# NitroxAnalyzer.net
KiCad netlist of a schematic drawn in EAGLE
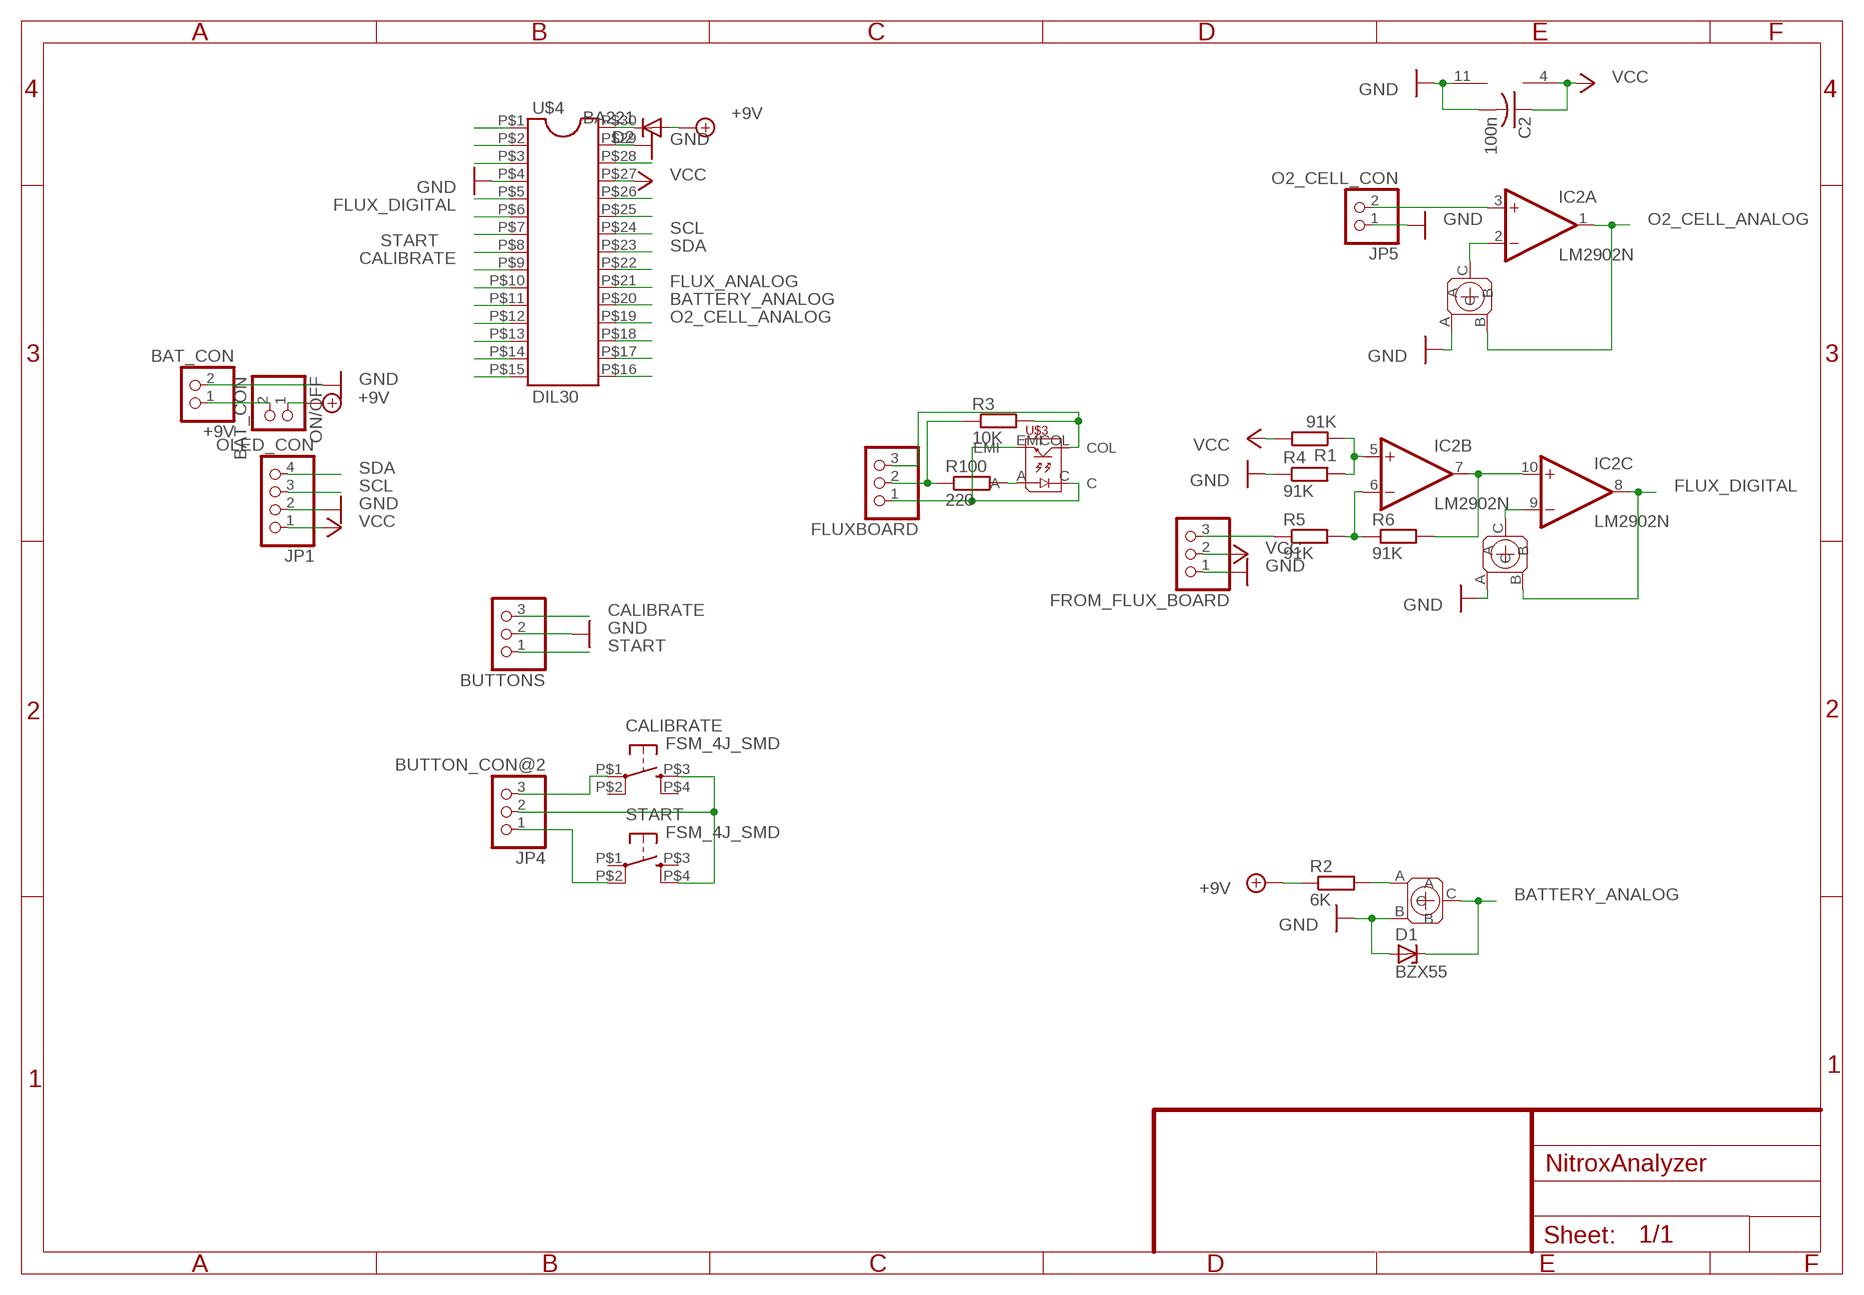
[diagram p0: schematic, sheet 1]

(export (version "E")
  (design (tool "Eeschema 10.0.6"))
  (components
    (comp (ref "+9V")
      (value "BAT_CON")
      (footprint "eagle-import:1X02")
      (libsource (lib "eagle-import") (part "PINHD-1X2"))
    )
    (comp (ref "BUTTONS")
      (value "PINHD-1X3")
      (footprint "eagle-import:1X03")
      (libsource (lib "eagle-import") (part "PINHD-1X3"))
    )
    (comp (ref "C2")
      (value "100n")
      (footprint "eagle-import:C1206")
      (libsource (lib "eagle-import") (part "C-USC1206"))
    )
    (comp (ref "CALIBRATE")
      (value "FSM_4J_SMD")
      (footprint "eagle-import:B3F-10XX")
      (libsource (lib "eagle-import") (part "FSM_4J_SMD"))
    )
    (comp (ref "D1")
      (value "BZX55")
      (footprint "eagle-import:DO35Z10")
      (libsource (lib "eagle-import") (part "BZX55"))
    )
    (comp (ref "D2")
      (value "BA221")
      (footprint "eagle-import:DO35-10")
      (libsource (lib "eagle-import") (part "BA221"))
    )
    (comp (ref "FLUXBOARD")
      (value "PINHD-1X3")
      (footprint "eagle-import:1X03")
      (libsource (lib "eagle-import") (part "PINHD-1X3"))
    )
    (comp (ref "FROM_FLUX_BOARD")
      (value "PINHD-1X3")
      (footprint "eagle-import:1X03")
      (libsource (lib "eagle-import") (part "PINHD-1X3"))
    )
    (comp (ref "IC2")
      (value "LM2902N")
      (footprint "eagle-import:DIL14")
      (libsource (lib "eagle-import") (part "LM2902N"))
    )
    (comp (ref "JP1")
      (value "OLED_CON")
      (footprint "eagle-import:1X04")
      (libsource (lib "eagle-import") (part "PINHD-1X4"))
    )
    (comp (ref "JP4")
      (value "BUTTON_CON@2")
      (footprint "eagle-import:1X03")
      (libsource (lib "eagle-import") (part "PINHD-1X3"))
    )
    (comp (ref "JP5")
      (value "O2_CELL_CON")
      (footprint "eagle-import:1X02")
      (libsource (lib "eagle-import") (part "PINHD-1X2"))
    )
    (comp (ref "ON/OFF")
      (value "BAT_CON")
      (footprint "eagle-import:1X02")
      (libsource (lib "eagle-import") (part "PINHD-1X2"))
    )
    (comp (ref "R1")
      (value "91K")
      (footprint "eagle-import:R0805")
      (libsource (lib "eagle-import") (part "R-EU_R0805"))
    )
    (comp (ref "R2")
      (value "6K")
      (footprint "eagle-import:R1206")
      (libsource (lib "eagle-import") (part "R-EU_R1206"))
    )
    (comp (ref "R3")
      (value "10K")
      (footprint "eagle-import:R1206")
      (libsource (lib "eagle-import") (part "R-EU_R1206"))
    )
    (comp (ref "R4")
      (value "91K")
      (footprint "eagle-import:R0805")
      (libsource (lib "eagle-import") (part "R-EU_R0805"))
    )
    (comp (ref "R5")
      (value "91K")
      (footprint "eagle-import:R0805")
      (libsource (lib "eagle-import") (part "R-EU_R0805"))
    )
    (comp (ref "R6")
      (value "91K")
      (footprint "eagle-import:R0805")
      (libsource (lib "eagle-import") (part "R-EU_R0805"))
    )
    (comp (ref "R100")
      (value "220")
      (footprint "eagle-import:R1206")
      (libsource (lib "eagle-import") (part "R-EU_R1206"))
    )
    (comp (ref "START")
      (value "FSM_4J_SMD")
      (footprint "eagle-import:B3F-10XX")
      (libsource (lib "eagle-import") (part "FSM_4J_SMD"))
    )
    (comp (ref "U$1")
      (value "10K")
      (footprint "eagle-import:PT6KV")
      (libsource (lib "eagle-import") (part "PT6KV"))
    )
    (comp (ref "U$2")
      (value "100K")
      (footprint "eagle-import:PT6KV")
      (libsource (lib "eagle-import") (part "PT6KV"))
    )
    (comp (ref "U$3")
      (value "ITR8307")
      (footprint "eagle-import:4PIN")
      (libsource (lib "eagle-import") (part "ITR8307"))
    )
    (comp (ref "U$4")
      (value "DIL30")
      (footprint "eagle-import:DIL30")
      (libsource (lib "eagle-import") (part "DIL30"))
    )
    (comp (ref "U$5")
      (value "100K")
      (footprint "eagle-import:PT6KV")
      (libsource (lib "eagle-import") (part "PT6KV"))
    )
  )
  (nets
    (net (code "1") (name "+9V") (class "Default")
      (node (ref "D2") (pin "A") (pinfunction "A_A") (pintype "passive"))
      (node (ref "ON/OFF") (pin "1") (pinfunction "1_1") (pintype "passive"))
      (node (ref "R2") (pin "1") (pinfunction "1_1") (pintype "passive"))
    )
    (net (code "2") (name "/BATTERY_ANALOG") (class "Default")
      (node (ref "D1") (pin "C") (pinfunction "C_C") (pintype "passive"))
      (node (ref "U$1") (pin "C") (pinfunction "C_C") (pintype "bidirectional"))
      (node (ref "U$4") (pin "P$20") (pinfunction "20_P$20") (pintype "passive"))
    )
    (net (code "3") (name "/CALIBRATE") (class "Default")
      (node (ref "BUTTONS") (pin "3") (pinfunction "3_3") (pintype "passive"))
      (node (ref "U$4") (pin "P$8") (pinfunction "8_P$8") (pintype "passive"))
    )
    (net (code "4") (name "/FLUX_ANALOG") (class "Default")
      (node (ref "U$4") (pin "P$21") (pinfunction "21_P$21") (pintype "passive"))
    )
    (net (code "5") (name "/FLUX_DIGITAL") (class "Default")
      (node (ref "IC2") (pin "8") (pinfunction "OUT_8") (pintype "output"))
      (node (ref "U$4") (pin "P$5") (pinfunction "5_P$5") (pintype "passive"))
      (node (ref "U$5") (pin "B") (pinfunction "B_B") (pintype "bidirectional"))
    )
    (net (code "6") (name "/O2_CELL_ANALOG") (class "Default")
      (node (ref "IC2") (pin "1") (pinfunction "OUT_1") (pintype "output"))
      (node (ref "U$2") (pin "B") (pinfunction "B_B") (pintype "bidirectional"))
      (node (ref "U$4") (pin "P$19") (pinfunction "19_P$19") (pintype "passive"))
    )
    (net (code "7") (name "/SCL") (class "Default")
      (node (ref "JP1") (pin "3") (pinfunction "3_3") (pintype "passive"))
      (node (ref "U$4") (pin "P$24") (pinfunction "24_P$24") (pintype "passive"))
    )
    (net (code "8") (name "/SDA") (class "Default")
      (node (ref "JP1") (pin "4") (pinfunction "4_4") (pintype "passive"))
      (node (ref "U$4") (pin "P$23") (pinfunction "23_P$23") (pintype "passive"))
    )
    (net (code "9") (name "/START") (class "Default")
      (node (ref "BUTTONS") (pin "1") (pinfunction "1_1") (pintype "passive"))
      (node (ref "U$4") (pin "P$7") (pinfunction "7_P$7") (pintype "passive"))
    )
    (net (code "10") (name "GND") (class "Default")
      (node (ref "+9V") (pin "2") (pinfunction "2_2") (pintype "passive"))
      (node (ref "BUTTONS") (pin "2") (pinfunction "2_2") (pintype "passive"))
      (node (ref "C2") (pin "2") (pinfunction "2_2") (pintype "passive"))
      (node (ref "D1") (pin "A") (pinfunction "A_A") (pintype "passive"))
      (node (ref "FROM_FLUX_BOARD") (pin "1") (pinfunction "1_1") (pintype "passive"))
      (node (ref "IC2") (pin "11") (pinfunction "V-_11") (pintype "power_in"))
      (node (ref "JP1") (pin "2") (pinfunction "2_2") (pintype "passive"))
      (node (ref "JP5") (pin "1") (pinfunction "1_1") (pintype "passive"))
      (node (ref "R4") (pin "1") (pinfunction "1_1") (pintype "passive"))
      (node (ref "U$1") (pin "B") (pinfunction "B_B") (pintype "bidirectional"))
      (node (ref "U$2") (pin "A") (pinfunction "A_A") (pintype "bidirectional"))
      (node (ref "U$4") (pin "P$29") (pinfunction "29_P$29") (pintype "passive"))
      (node (ref "U$4") (pin "P$4") (pinfunction "4_P$4") (pintype "passive"))
      (node (ref "U$5") (pin "A") (pinfunction "A_A") (pintype "bidirectional"))
    )
    (net (code "11") (name "Net-(+9V-Pad1)") (class "Default")
      (node (ref "+9V") (pin "1") (pinfunction "1_1") (pintype "passive"))
      (node (ref "ON/OFF") (pin "2") (pinfunction "2_2") (pintype "passive"))
    )
    (net (code "12") (name "Net-(CALIBRATE-P)") (class "Default")
      (node (ref "CALIBRATE") (pin "P$1") (pinfunction "P_P$1") (pintype "passive"))
      (node (ref "JP4") (pin "3") (pinfunction "3_3") (pintype "passive"))
    )
    (net (code "13") (name "Net-(CALIBRATE-S)") (class "Default")
      (node (ref "CALIBRATE") (pin "P$3") (pinfunction "S_P$3") (pintype "passive"))
      (node (ref "JP4") (pin "2") (pinfunction "2_2") (pintype "passive"))
      (node (ref "START") (pin "P$4") (pinfunction "S1_P$4") (pintype "passive"))
    )
    (net (code "14") (name "Net-(FLUXBOARD-Pad1)") (class "Default")
      (node (ref "FLUXBOARD") (pin "1") (pinfunction "1_1") (pintype "passive"))
      (node (ref "U$3") (pin "C") (pinfunction "C_C") (pintype "power_in"))
      (node (ref "U$3") (pin "EMI") (pinfunction "EMI_EMI") (pintype "power_in"))
    )
    (net (code "15") (name "Net-(FLUXBOARD-Pad2)") (class "Default")
      (node (ref "FLUXBOARD") (pin "2") (pinfunction "2_2") (pintype "passive"))
      (node (ref "R100") (pin "1") (pinfunction "1_1") (pintype "passive"))
      (node (ref "R3") (pin "1") (pinfunction "1_1") (pintype "passive"))
    )
    (net (code "16") (name "Net-(FLUXBOARD-Pad3)") (class "Default")
      (node (ref "FLUXBOARD") (pin "3") (pinfunction "3_3") (pintype "passive"))
      (node (ref "R3") (pin "2") (pinfunction "2_2") (pintype "passive"))
      (node (ref "U$3") (pin "COL") (pinfunction "COL_COL") (pintype "power_in"))
    )
    (net (code "17") (name "Net-(FROM_FLUX_BOARD-Pad3)") (class "Default")
      (node (ref "FROM_FLUX_BOARD") (pin "3") (pinfunction "3_3") (pintype "passive"))
      (node (ref "R5") (pin "1") (pinfunction "1_1") (pintype "passive"))
    )
    (net (code "18") (name "Net-(IC2A-+IN)") (class "Default")
      (node (ref "IC2") (pin "3") (pinfunction "+IN_3") (pintype "input"))
      (node (ref "JP5") (pin "2") (pinfunction "2_2") (pintype "passive"))
    )
    (net (code "19") (name "Net-(IC2A--IN)") (class "Default")
      (node (ref "IC2") (pin "2") (pinfunction "-IN_2") (pintype "input"))
      (node (ref "U$2") (pin "C") (pinfunction "C_C") (pintype "bidirectional"))
    )
    (net (code "20") (name "Net-(IC2B-+IN)") (class "Default")
      (node (ref "IC2") (pin "5") (pinfunction "+IN_5") (pintype "input"))
      (node (ref "R1") (pin "1") (pinfunction "1_1") (pintype "passive"))
      (node (ref "R4") (pin "2") (pinfunction "2_2") (pintype "passive"))
    )
    (net (code "21") (name "Net-(IC2B--IN)") (class "Default")
      (node (ref "IC2") (pin "6") (pinfunction "-IN_6") (pintype "input"))
      (node (ref "R5") (pin "2") (pinfunction "2_2") (pintype "passive"))
      (node (ref "R6") (pin "1") (pinfunction "1_1") (pintype "passive"))
    )
    (net (code "22") (name "Net-(IC2B-OUT)") (class "Default")
      (node (ref "IC2") (pin "10") (pinfunction "+IN_10") (pintype "input"))
      (node (ref "IC2") (pin "7") (pinfunction "OUT_7") (pintype "output"))
      (node (ref "R6") (pin "2") (pinfunction "2_2") (pintype "passive"))
    )
    (net (code "23") (name "Net-(IC2C--IN)") (class "Default")
      (node (ref "IC2") (pin "9") (pinfunction "-IN_9") (pintype "input"))
      (node (ref "U$5") (pin "C") (pinfunction "C_C") (pintype "bidirectional"))
    )
    (net (code "24") (name "Net-(R2-Pad2)") (class "Default")
      (node (ref "R2") (pin "2") (pinfunction "2_2") (pintype "passive"))
      (node (ref "U$1") (pin "A") (pinfunction "A_A") (pintype "bidirectional"))
    )
    (net (code "25") (name "Net-(R100-Pad2)") (class "Default")
      (node (ref "R100") (pin "2") (pinfunction "2_2") (pintype "passive"))
      (node (ref "U$3") (pin "A") (pinfunction "A_A") (pintype "power_in"))
    )
    (net (code "26") (name "Net-(START-P1)") (class "Default")
      (node (ref "JP4") (pin "1") (pinfunction "1_1") (pintype "passive"))
      (node (ref "START") (pin "P$2") (pinfunction "P1_P$2") (pintype "passive"))
    )
    (net (code "27") (name "Net-(U$4-30)") (class "Default")
      (node (ref "D2") (pin "C") (pinfunction "C_C") (pintype "passive"))
      (node (ref "U$4") (pin "P$30") (pinfunction "30_P$30") (pintype "passive"))
    )
    (net (code "28") (name "VCC") (class "Default")
      (node (ref "C2") (pin "1") (pinfunction "1_1") (pintype "passive"))
      (node (ref "FROM_FLUX_BOARD") (pin "2") (pinfunction "2_2") (pintype "passive"))
      (node (ref "IC2") (pin "4") (pinfunction "V+_4") (pintype "power_in"))
      (node (ref "JP1") (pin "1") (pinfunction "1_1") (pintype "passive"))
      (node (ref "R1") (pin "2") (pinfunction "2_2") (pintype "passive"))
      (node (ref "U$4") (pin "P$27") (pinfunction "27_P$27") (pintype "passive"))
    )
    (net (code "29") (name "unconnected-(CALIBRATE-P1-PadP$2)") (class "Default")
      (node (ref "CALIBRATE") (pin "P$2") (pinfunction "P1_P$2") (pintype "passive"))
    )
    (net (code "30") (name "unconnected-(CALIBRATE-S1-PadP$4)") (class "Default")
      (node (ref "CALIBRATE") (pin "P$4") (pinfunction "S1_P$4") (pintype "passive"))
    )
    (net (code "31") (name "unconnected-(START-P-PadP$1)") (class "Default")
      (node (ref "START") (pin "P$1") (pinfunction "P_P$1") (pintype "passive"))
    )
    (net (code "32") (name "unconnected-(START-S-PadP$3)") (class "Default")
      (node (ref "START") (pin "P$3") (pinfunction "S_P$3") (pintype "passive"))
    )
    (net (code "33") (name "unconnected-(U$4-1-PadP$1)") (class "Default")
      (node (ref "U$4") (pin "P$1") (pinfunction "1_P$1") (pintype "passive"))
    )
    (net (code "34") (name "unconnected-(U$4-2-PadP$2)") (class "Default")
      (node (ref "U$4") (pin "P$2") (pinfunction "2_P$2") (pintype "passive"))
    )
    (net (code "35") (name "unconnected-(U$4-3-PadP$3)") (class "Default")
      (node (ref "U$4") (pin "P$3") (pinfunction "3_P$3") (pintype "passive"))
    )
    (net (code "36") (name "unconnected-(U$4-6-PadP$6)") (class "Default")
      (node (ref "U$4") (pin "P$6") (pinfunction "6_P$6") (pintype "passive"))
    )
    (net (code "37") (name "unconnected-(U$4-9-PadP$9)") (class "Default")
      (node (ref "U$4") (pin "P$9") (pinfunction "9_P$9") (pintype "passive"))
    )
    (net (code "38") (name "unconnected-(U$4-10-PadP$10)") (class "Default")
      (node (ref "U$4") (pin "P$10") (pinfunction "10_P$10") (pintype "passive"))
    )
    (net (code "39") (name "unconnected-(U$4-11-PadP$11)") (class "Default")
      (node (ref "U$4") (pin "P$11") (pinfunction "11_P$11") (pintype "passive"))
    )
    (net (code "40") (name "unconnected-(U$4-12-PadP$12)") (class "Default")
      (node (ref "U$4") (pin "P$12") (pinfunction "12_P$12") (pintype "passive"))
    )
    (net (code "41") (name "unconnected-(U$4-13-PadP$13)") (class "Default")
      (node (ref "U$4") (pin "P$13") (pinfunction "13_P$13") (pintype "passive"))
    )
    (net (code "42") (name "unconnected-(U$4-14-PadP$14)") (class "Default")
      (node (ref "U$4") (pin "P$14") (pinfunction "14_P$14") (pintype "passive"))
    )
    (net (code "43") (name "unconnected-(U$4-15-PadP$15)") (class "Default")
      (node (ref "U$4") (pin "P$15") (pinfunction "15_P$15") (pintype "passive"))
    )
    (net (code "44") (name "unconnected-(U$4-16-PadP$16)") (class "Default")
      (node (ref "U$4") (pin "P$16") (pinfunction "16_P$16") (pintype "passive"))
    )
    (net (code "45") (name "unconnected-(U$4-17-PadP$17)") (class "Default")
      (node (ref "U$4") (pin "P$17") (pinfunction "17_P$17") (pintype "passive"))
    )
    (net (code "46") (name "unconnected-(U$4-18-PadP$18)") (class "Default")
      (node (ref "U$4") (pin "P$18") (pinfunction "18_P$18") (pintype "passive"))
    )
    (net (code "47") (name "unconnected-(U$4-22-PadP$22)") (class "Default")
      (node (ref "U$4") (pin "P$22") (pinfunction "22_P$22") (pintype "passive"))
    )
    (net (code "48") (name "unconnected-(U$4-25-PadP$25)") (class "Default")
      (node (ref "U$4") (pin "P$25") (pinfunction "25_P$25") (pintype "passive"))
    )
    (net (code "49") (name "unconnected-(U$4-26-PadP$26)") (class "Default")
      (node (ref "U$4") (pin "P$26") (pinfunction "26_P$26") (pintype "passive"))
    )
    (net (code "50") (name "unconnected-(U$4-28-PadP$28)") (class "Default")
      (node (ref "U$4") (pin "P$28") (pinfunction "28_P$28") (pintype "passive"))
    )
  )
)
